# Swagelock_controller.net
KiCad netlist of a schematic drawn in EAGLE
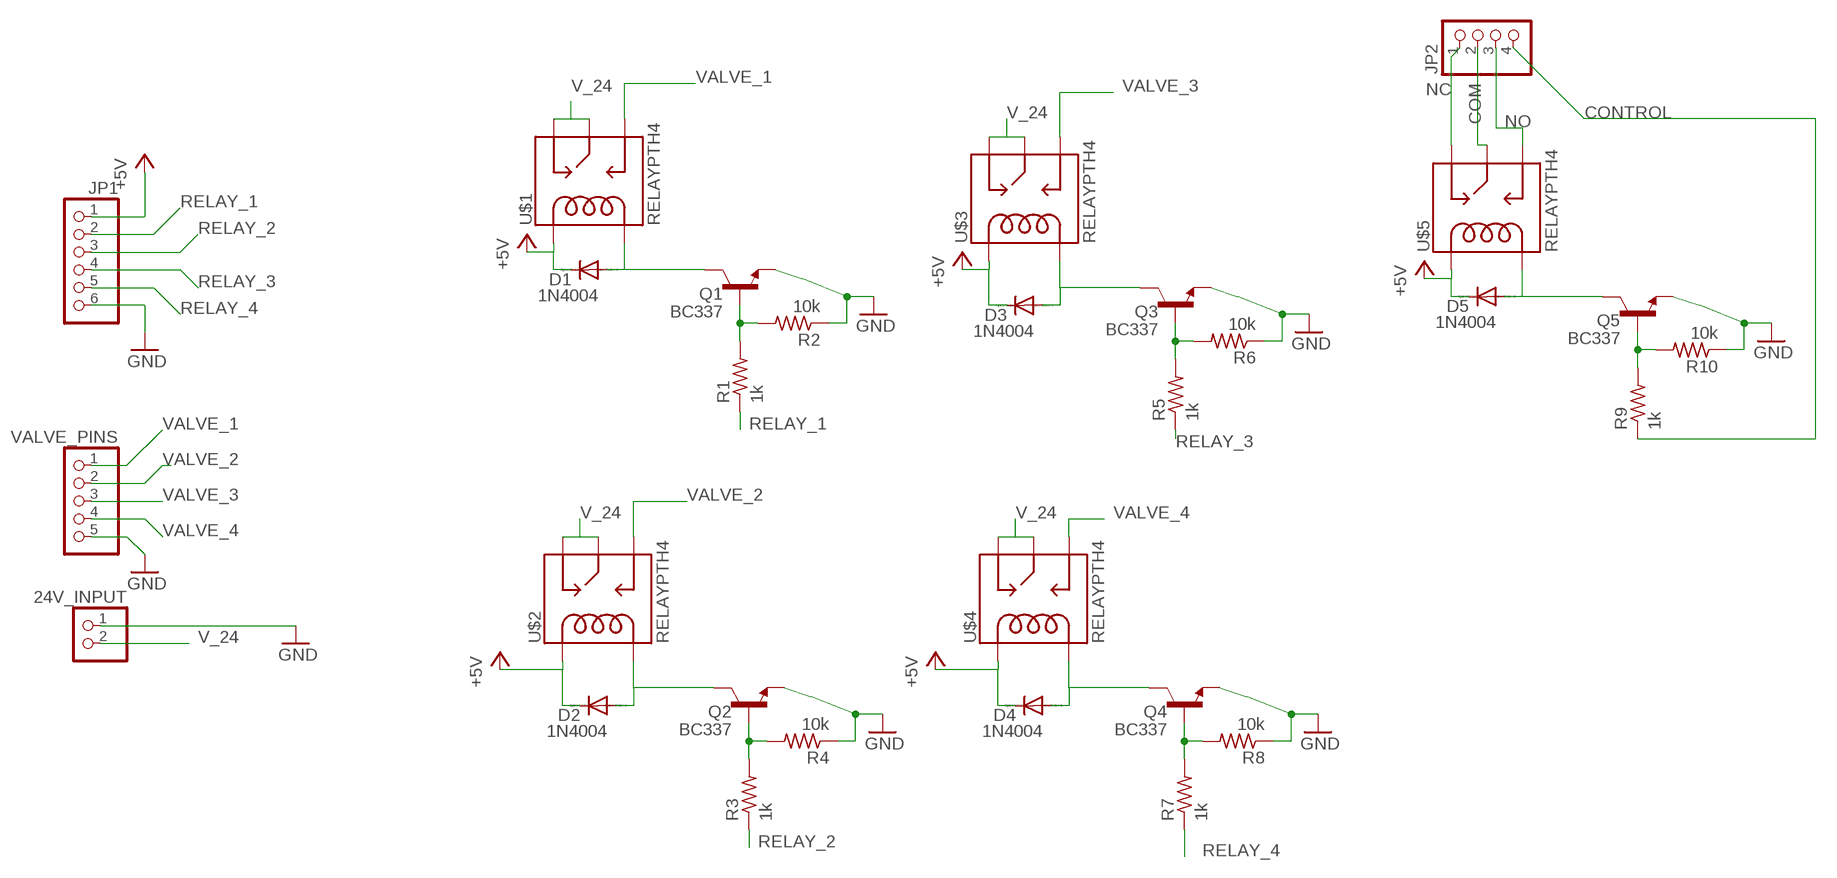
[diagram p0: schematic, sheet 1]

(export (version "E")
  (design (tool "Eeschema 10.0.6"))
  (components
    (comp (ref "24V_INPUT")
      (value "PINHD-1X2")
      (footprint "eagle-import:1X02")
      (libsource (lib "eagle-import") (part "PINHD-1X2"))
    )
    (comp (ref "D1")
      (value "1N4004")
      (footprint "eagle-import:DO41-10")
      (libsource (lib "eagle-import") (part "1N4004"))
    )
    (comp (ref "D2")
      (value "1N4004")
      (footprint "eagle-import:DO41-10")
      (libsource (lib "eagle-import") (part "1N4004"))
    )
    (comp (ref "D3")
      (value "1N4004")
      (footprint "eagle-import:DO41-10")
      (libsource (lib "eagle-import") (part "1N4004"))
    )
    (comp (ref "D4")
      (value "1N4004")
      (footprint "eagle-import:DO41-10")
      (libsource (lib "eagle-import") (part "1N4004"))
    )
    (comp (ref "D5")
      (value "1N4004")
      (footprint "eagle-import:DO41-10")
      (libsource (lib "eagle-import") (part "1N4004"))
    )
    (comp (ref "JP1")
      (value "PINHD-1X6")
      (footprint "eagle-import:1X06")
      (libsource (lib "eagle-import") (part "PINHD-1X6"))
    )
    (comp (ref "JP2")
      (value "PINHD-1X4")
      (footprint "eagle-import:1X04")
      (libsource (lib "eagle-import") (part "PINHD-1X4"))
    )
    (comp (ref "Q1")
      (value "BC337")
      (footprint "eagle-import:TO92")
      (libsource (lib "eagle-import") (part "BC337"))
    )
    (comp (ref "Q2")
      (value "BC337")
      (footprint "eagle-import:TO92")
      (libsource (lib "eagle-import") (part "BC337"))
    )
    (comp (ref "Q3")
      (value "BC337")
      (footprint "eagle-import:TO92")
      (libsource (lib "eagle-import") (part "BC337"))
    )
    (comp (ref "Q4")
      (value "BC337")
      (footprint "eagle-import:TO92")
      (libsource (lib "eagle-import") (part "BC337"))
    )
    (comp (ref "Q5")
      (value "BC337")
      (footprint "eagle-import:TO92")
      (libsource (lib "eagle-import") (part "BC337"))
    )
    (comp (ref "R1")
      (value "1k")
      (footprint "eagle-import:0204_5")
      (libsource (lib "eagle-import") (part "R-US_0204/5"))
    )
    (comp (ref "R2")
      (value "10k")
      (footprint "eagle-import:0204_5")
      (libsource (lib "eagle-import") (part "R-US_0204/5"))
    )
    (comp (ref "R3")
      (value "1k")
      (footprint "eagle-import:0204_5")
      (libsource (lib "eagle-import") (part "R-US_0204/5"))
    )
    (comp (ref "R4")
      (value "10k")
      (footprint "eagle-import:0204_5")
      (libsource (lib "eagle-import") (part "R-US_0204/5"))
    )
    (comp (ref "R5")
      (value "1k")
      (footprint "eagle-import:0204_5")
      (libsource (lib "eagle-import") (part "R-US_0204/5"))
    )
    (comp (ref "R6")
      (value "10k")
      (footprint "eagle-import:0204_5")
      (libsource (lib "eagle-import") (part "R-US_0204/5"))
    )
    (comp (ref "R7")
      (value "1k")
      (footprint "eagle-import:0204_5")
      (libsource (lib "eagle-import") (part "R-US_0204/5"))
    )
    (comp (ref "R8")
      (value "10k")
      (footprint "eagle-import:0204_5")
      (libsource (lib "eagle-import") (part "R-US_0204/5"))
    )
    (comp (ref "R9")
      (value "1k")
      (footprint "eagle-import:0204_5")
      (libsource (lib "eagle-import") (part "R-US_0204/5"))
    )
    (comp (ref "R10")
      (value "10k")
      (footprint "eagle-import:0204_5")
      (libsource (lib "eagle-import") (part "R-US_0204/5"))
    )
    (comp (ref "U$1")
      (value "RELAYPTH4")
      (footprint "eagle-import:RELAY-JZC")
      (libsource (lib "eagle-import") (part "RELAYPTH4"))
    )
    (comp (ref "U$2")
      (value "RELAYPTH4")
      (footprint "eagle-import:RELAY-JZC")
      (libsource (lib "eagle-import") (part "RELAYPTH4"))
    )
    (comp (ref "U$3")
      (value "RELAYPTH4")
      (footprint "eagle-import:RELAY-JZC")
      (libsource (lib "eagle-import") (part "RELAYPTH4"))
    )
    (comp (ref "U$4")
      (value "RELAYPTH4")
      (footprint "eagle-import:RELAY-JZC")
      (libsource (lib "eagle-import") (part "RELAYPTH4"))
    )
    (comp (ref "U$5")
      (value "RELAYPTH4")
      (footprint "eagle-import:RELAY-JZC")
      (libsource (lib "eagle-import") (part "RELAYPTH4"))
    )
    (comp (ref "VALVE_PINS")
      (value "PINHD-1X5")
      (footprint "eagle-import:1X05")
      (libsource (lib "eagle-import") (part "PINHD-1X5"))
    )
  )
  (nets
    (net (code "1") (name "+5V") (class "Default")
      (node (ref "D1") (pin "C") (pinfunction "C_C") (pintype "passive"))
      (node (ref "D2") (pin "C") (pinfunction "C_C") (pintype "passive"))
      (node (ref "D3") (pin "C") (pinfunction "C_C") (pintype "passive"))
      (node (ref "D4") (pin "C") (pinfunction "C_C") (pintype "passive"))
      (node (ref "D5") (pin "C") (pinfunction "C_C") (pintype "passive"))
      (node (ref "JP1") (pin "1") (pinfunction "1_1") (pintype "passive"))
      (node (ref "U$1") (pin "5") (pinfunction "COIL1_5") (pintype "bidirectional"))
      (node (ref "U$2") (pin "5") (pinfunction "COIL1_5") (pintype "bidirectional"))
      (node (ref "U$3") (pin "5") (pinfunction "COIL1_5") (pintype "bidirectional"))
      (node (ref "U$4") (pin "5") (pinfunction "COIL1_5") (pintype "bidirectional"))
      (node (ref "U$5") (pin "5") (pinfunction "COIL1_5") (pintype "bidirectional"))
    )
    (net (code "2") (name "COM") (class "Default")
      (node (ref "JP2") (pin "2") (pinfunction "2_2") (pintype "passive"))
      (node (ref "U$5") (pin "4") (pinfunction "MAIN_4") (pintype "bidirectional"))
    )
    (net (code "3") (name "CONTROL") (class "Default")
      (node (ref "JP2") (pin "4") (pinfunction "4_4") (pintype "passive"))
      (node (ref "R9") (pin "1") (pinfunction "1_1") (pintype "passive"))
    )
    (net (code "4") (name "GND") (class "Default")
      (node (ref "24V_INPUT") (pin "1") (pinfunction "1_1") (pintype "passive"))
      (node (ref "JP1") (pin "6") (pinfunction "6_6") (pintype "passive"))
      (node (ref "Q1") (pin "1") (pinfunction "E_1") (pintype "passive"))
      (node (ref "Q2") (pin "1") (pinfunction "E_1") (pintype "passive"))
      (node (ref "Q3") (pin "1") (pinfunction "E_1") (pintype "passive"))
      (node (ref "Q4") (pin "1") (pinfunction "E_1") (pintype "passive"))
      (node (ref "Q5") (pin "1") (pinfunction "E_1") (pintype "passive"))
      (node (ref "R10") (pin "1") (pinfunction "1_1") (pintype "passive"))
      (node (ref "R2") (pin "1") (pinfunction "1_1") (pintype "passive"))
      (node (ref "R4") (pin "1") (pinfunction "1_1") (pintype "passive"))
      (node (ref "R6") (pin "1") (pinfunction "1_1") (pintype "passive"))
      (node (ref "R8") (pin "1") (pinfunction "1_1") (pintype "passive"))
      (node (ref "VALVE_PINS") (pin "5") (pinfunction "5_5") (pintype "passive"))
    )
    (net (code "5") (name "NC") (class "Default")
      (node (ref "JP2") (pin "1") (pinfunction "1_1") (pintype "passive"))
      (node (ref "U$5") (pin "2") (pinfunction "NC_2") (pintype "bidirectional"))
    )
    (net (code "6") (name "NO") (class "Default")
      (node (ref "JP2") (pin "3") (pinfunction "3_3") (pintype "passive"))
      (node (ref "U$5") (pin "3") (pinfunction "NO_3") (pintype "bidirectional"))
    )
    (net (code "7") (name "Net-(Q1-B)") (class "Default")
      (node (ref "Q1") (pin "2") (pinfunction "B_2") (pintype "passive"))
      (node (ref "R1") (pin "2") (pinfunction "2_2") (pintype "passive"))
      (node (ref "R2") (pin "2") (pinfunction "2_2") (pintype "passive"))
    )
    (net (code "8") (name "Net-(Q1-C)") (class "Default")
      (node (ref "D1") (pin "A") (pinfunction "A_A") (pintype "passive"))
      (node (ref "Q1") (pin "3") (pinfunction "C_3") (pintype "passive"))
      (node (ref "U$1") (pin "1") (pinfunction "COIL2_1") (pintype "bidirectional"))
    )
    (net (code "9") (name "Net-(Q2-B)") (class "Default")
      (node (ref "Q2") (pin "2") (pinfunction "B_2") (pintype "passive"))
      (node (ref "R3") (pin "2") (pinfunction "2_2") (pintype "passive"))
      (node (ref "R4") (pin "2") (pinfunction "2_2") (pintype "passive"))
    )
    (net (code "10") (name "Net-(Q2-C)") (class "Default")
      (node (ref "D2") (pin "A") (pinfunction "A_A") (pintype "passive"))
      (node (ref "Q2") (pin "3") (pinfunction "C_3") (pintype "passive"))
      (node (ref "U$2") (pin "1") (pinfunction "COIL2_1") (pintype "bidirectional"))
    )
    (net (code "11") (name "Net-(Q3-B)") (class "Default")
      (node (ref "Q3") (pin "2") (pinfunction "B_2") (pintype "passive"))
      (node (ref "R5") (pin "2") (pinfunction "2_2") (pintype "passive"))
      (node (ref "R6") (pin "2") (pinfunction "2_2") (pintype "passive"))
    )
    (net (code "12") (name "Net-(Q3-C)") (class "Default")
      (node (ref "D3") (pin "A") (pinfunction "A_A") (pintype "passive"))
      (node (ref "Q3") (pin "3") (pinfunction "C_3") (pintype "passive"))
      (node (ref "U$3") (pin "1") (pinfunction "COIL2_1") (pintype "bidirectional"))
    )
    (net (code "13") (name "Net-(Q4-B)") (class "Default")
      (node (ref "Q4") (pin "2") (pinfunction "B_2") (pintype "passive"))
      (node (ref "R7") (pin "2") (pinfunction "2_2") (pintype "passive"))
      (node (ref "R8") (pin "2") (pinfunction "2_2") (pintype "passive"))
    )
    (net (code "14") (name "Net-(Q4-C)") (class "Default")
      (node (ref "D4") (pin "A") (pinfunction "A_A") (pintype "passive"))
      (node (ref "Q4") (pin "3") (pinfunction "C_3") (pintype "passive"))
      (node (ref "U$4") (pin "1") (pinfunction "COIL2_1") (pintype "bidirectional"))
    )
    (net (code "15") (name "Net-(Q5-B)") (class "Default")
      (node (ref "Q5") (pin "2") (pinfunction "B_2") (pintype "passive"))
      (node (ref "R10") (pin "2") (pinfunction "2_2") (pintype "passive"))
      (node (ref "R9") (pin "2") (pinfunction "2_2") (pintype "passive"))
    )
    (net (code "16") (name "Net-(Q5-C)") (class "Default")
      (node (ref "D5") (pin "A") (pinfunction "A_A") (pintype "passive"))
      (node (ref "Q5") (pin "3") (pinfunction "C_3") (pintype "passive"))
      (node (ref "U$5") (pin "1") (pinfunction "COIL2_1") (pintype "bidirectional"))
    )
    (net (code "17") (name "RELAY_1") (class "Default")
      (node (ref "JP1") (pin "2") (pinfunction "2_2") (pintype "passive"))
      (node (ref "R1") (pin "1") (pinfunction "1_1") (pintype "passive"))
    )
    (net (code "18") (name "RELAY_2") (class "Default")
      (node (ref "JP1") (pin "3") (pinfunction "3_3") (pintype "passive"))
      (node (ref "R3") (pin "1") (pinfunction "1_1") (pintype "passive"))
    )
    (net (code "19") (name "RELAY_3") (class "Default")
      (node (ref "JP1") (pin "4") (pinfunction "4_4") (pintype "passive"))
      (node (ref "R5") (pin "1") (pinfunction "1_1") (pintype "passive"))
    )
    (net (code "20") (name "RELAY_4") (class "Default")
      (node (ref "JP1") (pin "5") (pinfunction "5_5") (pintype "passive"))
      (node (ref "R7") (pin "1") (pinfunction "1_1") (pintype "passive"))
    )
    (net (code "21") (name "VALVE_1") (class "Default")
      (node (ref "U$1") (pin "3") (pinfunction "NO_3") (pintype "bidirectional"))
      (node (ref "VALVE_PINS") (pin "1") (pinfunction "1_1") (pintype "passive"))
    )
    (net (code "22") (name "VALVE_2") (class "Default")
      (node (ref "U$2") (pin "3") (pinfunction "NO_3") (pintype "bidirectional"))
      (node (ref "VALVE_PINS") (pin "2") (pinfunction "2_2") (pintype "passive"))
    )
    (net (code "23") (name "VALVE_3") (class "Default")
      (node (ref "U$3") (pin "3") (pinfunction "NO_3") (pintype "bidirectional"))
      (node (ref "VALVE_PINS") (pin "3") (pinfunction "3_3") (pintype "passive"))
    )
    (net (code "24") (name "VALVE_4") (class "Default")
      (node (ref "U$4") (pin "3") (pinfunction "NO_3") (pintype "bidirectional"))
      (node (ref "VALVE_PINS") (pin "4") (pinfunction "4_4") (pintype "passive"))
    )
    (net (code "25") (name "V_24") (class "Default")
      (node (ref "24V_INPUT") (pin "2") (pinfunction "2_2") (pintype "passive"))
      (node (ref "U$1") (pin "2") (pinfunction "NC_2") (pintype "bidirectional"))
      (node (ref "U$1") (pin "4") (pinfunction "MAIN_4") (pintype "bidirectional"))
      (node (ref "U$2") (pin "2") (pinfunction "NC_2") (pintype "bidirectional"))
      (node (ref "U$2") (pin "4") (pinfunction "MAIN_4") (pintype "bidirectional"))
      (node (ref "U$3") (pin "2") (pinfunction "NC_2") (pintype "bidirectional"))
      (node (ref "U$3") (pin "4") (pinfunction "MAIN_4") (pintype "bidirectional"))
      (node (ref "U$4") (pin "2") (pinfunction "NC_2") (pintype "bidirectional"))
      (node (ref "U$4") (pin "4") (pinfunction "MAIN_4") (pintype "bidirectional"))
    )
  )
)
